# fpga32-serdes-power.net
KiCad netlist of a schematic drawn in Altium Designer
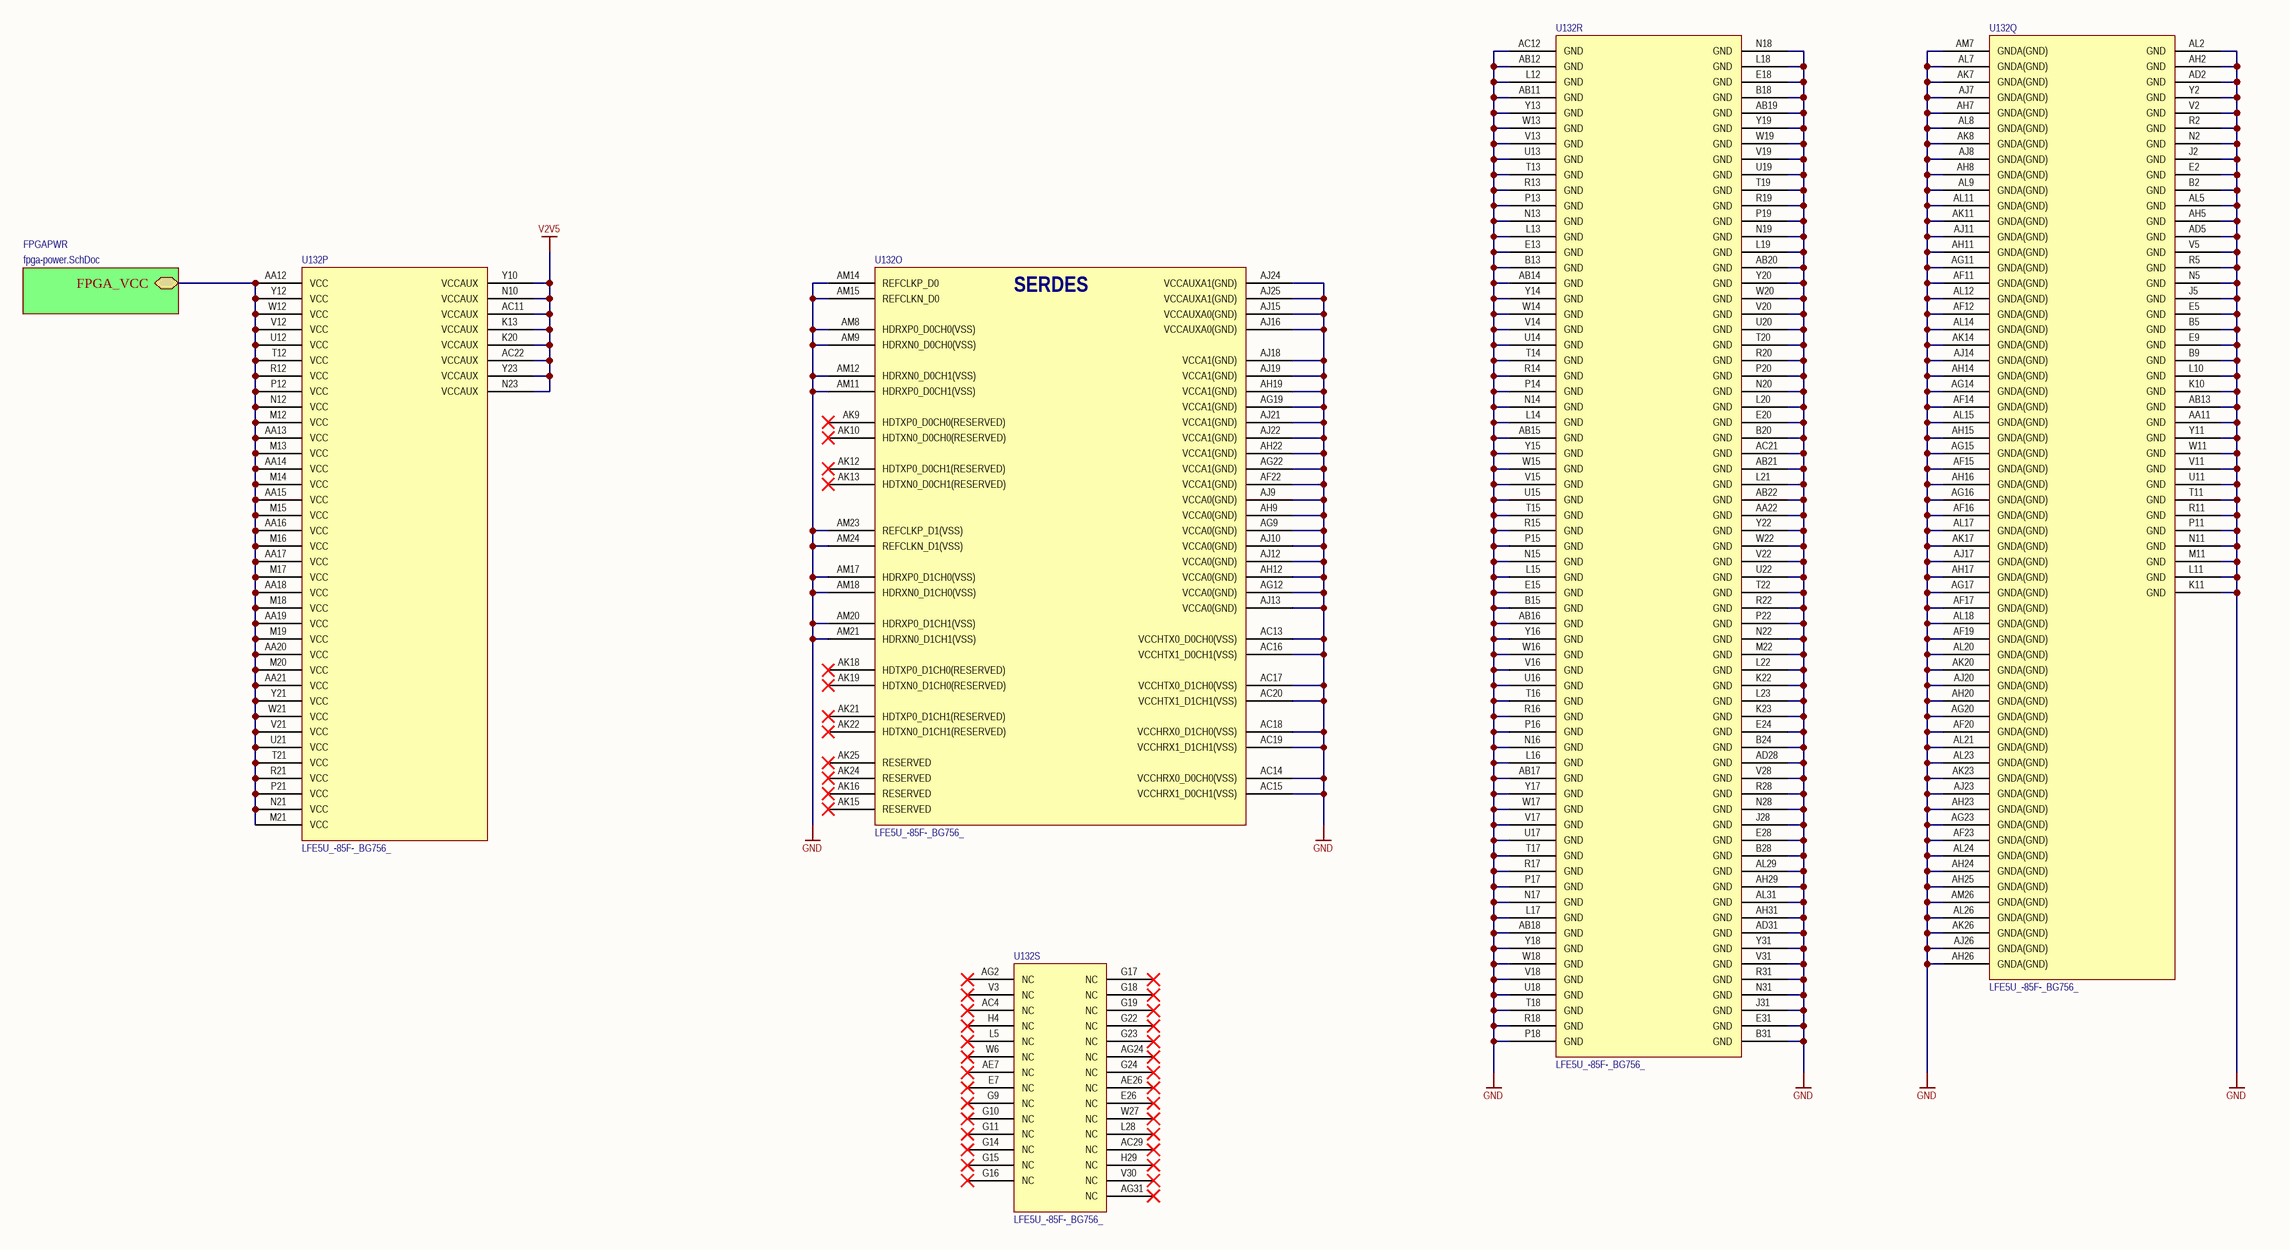
[diagram p0: fpga32-serdes-power.SchDoc]

(export (version "E")
  (design (tool "Eeschema 10.0.6"))
  (components
    (comp (ref "U132")
      (value "LFE5U_-85F-_BG756_")
      (footprint "lattice:caBGA756")
      (description "ECP5 FPGA, 85k LUT, 756-caBGA")
      (fields (field (name "MANUFACTURER") "Lattice Semiconductor"))
      (libsource (lib "lattice") (part "LFE5U_-85F-_BG756_"))
    )
  )
  (nets
    (net (code "1") (name "/FPGA_VCC") (class "Default")
      (node (ref "U132") (pin "AA12") (pinfunction "VCC_AA12") (pintype "power_in"))
      (node (ref "U132") (pin "AA13") (pinfunction "VCC_AA13") (pintype "power_in"))
      (node (ref "U132") (pin "AA14") (pinfunction "VCC_AA14") (pintype "power_in"))
      (node (ref "U132") (pin "AA15") (pinfunction "VCC_AA15") (pintype "power_in"))
      (node (ref "U132") (pin "AA16") (pinfunction "VCC_AA16") (pintype "power_in"))
      (node (ref "U132") (pin "AA17") (pinfunction "VCC_AA17") (pintype "power_in"))
      (node (ref "U132") (pin "AA18") (pinfunction "VCC_AA18") (pintype "power_in"))
      (node (ref "U132") (pin "AA19") (pinfunction "VCC_AA19") (pintype "power_in"))
      (node (ref "U132") (pin "AA20") (pinfunction "VCC_AA20") (pintype "power_in"))
      (node (ref "U132") (pin "AA21") (pinfunction "VCC_AA21") (pintype "power_in"))
      (node (ref "U132") (pin "M12") (pinfunction "VCC_M12") (pintype "power_in"))
      (node (ref "U132") (pin "M13") (pinfunction "VCC_M13") (pintype "power_in"))
      (node (ref "U132") (pin "M14") (pinfunction "VCC_M14") (pintype "power_in"))
      (node (ref "U132") (pin "M15") (pinfunction "VCC_M15") (pintype "power_in"))
      (node (ref "U132") (pin "M16") (pinfunction "VCC_M16") (pintype "power_in"))
      (node (ref "U132") (pin "M17") (pinfunction "VCC_M17") (pintype "power_in"))
      (node (ref "U132") (pin "M18") (pinfunction "VCC_M18") (pintype "power_in"))
      (node (ref "U132") (pin "M19") (pinfunction "VCC_M19") (pintype "power_in"))
      (node (ref "U132") (pin "M20") (pinfunction "VCC_M20") (pintype "power_in"))
      (node (ref "U132") (pin "M21") (pinfunction "VCC_M21") (pintype "power_in"))
      (node (ref "U132") (pin "N12") (pinfunction "VCC_N12") (pintype "power_in"))
      (node (ref "U132") (pin "N21") (pinfunction "VCC_N21") (pintype "power_in"))
      (node (ref "U132") (pin "P12") (pinfunction "VCC_P12") (pintype "power_in"))
      (node (ref "U132") (pin "P21") (pinfunction "VCC_P21") (pintype "power_in"))
      (node (ref "U132") (pin "R12") (pinfunction "VCC_R12") (pintype "power_in"))
      (node (ref "U132") (pin "R21") (pinfunction "VCC_R21") (pintype "power_in"))
      (node (ref "U132") (pin "T12") (pinfunction "VCC_T12") (pintype "power_in"))
      (node (ref "U132") (pin "T21") (pinfunction "VCC_T21") (pintype "power_in"))
      (node (ref "U132") (pin "U12") (pinfunction "VCC_U12") (pintype "power_in"))
      (node (ref "U132") (pin "U21") (pinfunction "VCC_U21") (pintype "power_in"))
      (node (ref "U132") (pin "V12") (pinfunction "VCC_V12") (pintype "power_in"))
      (node (ref "U132") (pin "V21") (pinfunction "VCC_V21") (pintype "power_in"))
      (node (ref "U132") (pin "W12") (pinfunction "VCC_W12") (pintype "power_in"))
      (node (ref "U132") (pin "W21") (pinfunction "VCC_W21") (pintype "power_in"))
      (node (ref "U132") (pin "Y12") (pinfunction "VCC_Y12") (pintype "power_in"))
      (node (ref "U132") (pin "Y21") (pinfunction "VCC_Y21") (pintype "power_in"))
    )
    (net (code "2") (name "GND") (class "Default")
      (node (ref "U132") (pin "AA11") (pinfunction "GND_AA11") (pintype "power_in"))
      (node (ref "U132") (pin "AA22") (pinfunction "GND_AA22") (pintype "power_in"))
      (node (ref "U132") (pin "AB11") (pinfunction "GND_AB11") (pintype "power_in"))
      (node (ref "U132") (pin "AB12") (pinfunction "GND_AB12") (pintype "power_in"))
      (node (ref "U132") (pin "AB13") (pinfunction "GND_AB13") (pintype "power_in"))
      (node (ref "U132") (pin "AB14") (pinfunction "GND_AB14") (pintype "power_in"))
      (node (ref "U132") (pin "AB15") (pinfunction "GND_AB15") (pintype "power_in"))
      (node (ref "U132") (pin "AB16") (pinfunction "GND_AB16") (pintype "power_in"))
      (node (ref "U132") (pin "AB17") (pinfunction "GND_AB17") (pintype "power_in"))
      (node (ref "U132") (pin "AB18") (pinfunction "GND_AB18") (pintype "power_in"))
      (node (ref "U132") (pin "AB19") (pinfunction "GND_AB19") (pintype "power_in"))
      (node (ref "U132") (pin "AB20") (pinfunction "GND_AB20") (pintype "power_in"))
      (node (ref "U132") (pin "AB21") (pinfunction "GND_AB21") (pintype "power_in"))
      (node (ref "U132") (pin "AB22") (pinfunction "GND_AB22") (pintype "power_in"))
      (node (ref "U132") (pin "AC12") (pinfunction "GND_AC12") (pintype "power_in"))
      (node (ref "U132") (pin "AC13") (pinfunction "VCCHTX0_D0CH0(VSS)_AC13") (pintype "power_in"))
      (node (ref "U132") (pin "AC14") (pinfunction "VCCHRX0_D0CH0(VSS)_AC14") (pintype "power_in"))
      (node (ref "U132") (pin "AC15") (pinfunction "VCCHRX1_D0CH1(VSS)_AC15") (pintype "power_in"))
      (node (ref "U132") (pin "AC16") (pinfunction "VCCHTX1_D0CH1(VSS)_AC16") (pintype "power_in"))
      (node (ref "U132") (pin "AC17") (pinfunction "VCCHTX0_D1CH0(VSS)_AC17") (pintype "power_in"))
      (node (ref "U132") (pin "AC18") (pinfunction "VCCHRX0_D1CH0(VSS)_AC18") (pintype "power_in"))
      (node (ref "U132") (pin "AC19") (pinfunction "VCCHRX1_D1CH1(VSS)_AC19") (pintype "power_in"))
      (node (ref "U132") (pin "AC20") (pinfunction "VCCHTX1_D1CH1(VSS)_AC20") (pintype "power_in"))
      (node (ref "U132") (pin "AC21") (pinfunction "GND_AC21") (pintype "power_in"))
      (node (ref "U132") (pin "AD2") (pinfunction "GND_AD2") (pintype "power_in"))
      (node (ref "U132") (pin "AD28") (pinfunction "GND_AD28") (pintype "power_in"))
      (node (ref "U132") (pin "AD31") (pinfunction "GND_AD31") (pintype "power_in"))
      (node (ref "U132") (pin "AD5") (pinfunction "GND_AD5") (pintype "power_in"))
      (node (ref "U132") (pin "AF11") (pinfunction "GNDA(GND)_AF11") (pintype "power_in"))
      (node (ref "U132") (pin "AF12") (pinfunction "GNDA(GND)_AF12") (pintype "power_in"))
      (node (ref "U132") (pin "AF14") (pinfunction "GNDA(GND)_AF14") (pintype "power_in"))
      (node (ref "U132") (pin "AF15") (pinfunction "GNDA(GND)_AF15") (pintype "power_in"))
      (node (ref "U132") (pin "AF16") (pinfunction "GNDA(GND)_AF16") (pintype "power_in"))
      (node (ref "U132") (pin "AF17") (pinfunction "GNDA(GND)_AF17") (pintype "power_in"))
      (node (ref "U132") (pin "AF19") (pinfunction "GNDA(GND)_AF19") (pintype "power_in"))
      (node (ref "U132") (pin "AF20") (pinfunction "GNDA(GND)_AF20") (pintype "power_in"))
      (node (ref "U132") (pin "AF22") (pinfunction "VCCA1(GND)_AF22") (pintype "power_in"))
      (node (ref "U132") (pin "AF23") (pinfunction "GNDA(GND)_AF23") (pintype "power_in"))
      (node (ref "U132") (pin "AG11") (pinfunction "GNDA(GND)_AG11") (pintype "power_in"))
      (node (ref "U132") (pin "AG12") (pinfunction "VCCA0(GND)_AG12") (pintype "power_in"))
      (node (ref "U132") (pin "AG14") (pinfunction "GNDA(GND)_AG14") (pintype "power_in"))
      (node (ref "U132") (pin "AG15") (pinfunction "GNDA(GND)_AG15") (pintype "power_in"))
      (node (ref "U132") (pin "AG16") (pinfunction "GNDA(GND)_AG16") (pintype "power_in"))
      (node (ref "U132") (pin "AG17") (pinfunction "GNDA(GND)_AG17") (pintype "power_in"))
      (node (ref "U132") (pin "AG19") (pinfunction "VCCA1(GND)_AG19") (pintype "power_in"))
      (node (ref "U132") (pin "AG20") (pinfunction "GNDA(GND)_AG20") (pintype "power_in"))
      (node (ref "U132") (pin "AG22") (pinfunction "VCCA1(GND)_AG22") (pintype "power_in"))
      (node (ref "U132") (pin "AG23") (pinfunction "GNDA(GND)_AG23") (pintype "power_in"))
      (node (ref "U132") (pin "AG9") (pinfunction "VCCA0(GND)_AG9") (pintype "power_in"))
      (node (ref "U132") (pin "AH11") (pinfunction "GNDA(GND)_AH11") (pintype "power_in"))
      (node (ref "U132") (pin "AH12") (pinfunction "VCCA0(GND)_AH12") (pintype "power_in"))
      (node (ref "U132") (pin "AH14") (pinfunction "GNDA(GND)_AH14") (pintype "power_in"))
      (node (ref "U132") (pin "AH15") (pinfunction "GNDA(GND)_AH15") (pintype "power_in"))
      (node (ref "U132") (pin "AH16") (pinfunction "GNDA(GND)_AH16") (pintype "power_in"))
      (node (ref "U132") (pin "AH17") (pinfunction "GNDA(GND)_AH17") (pintype "power_in"))
      (node (ref "U132") (pin "AH19") (pinfunction "VCCA1(GND)_AH19") (pintype "power_in"))
      (node (ref "U132") (pin "AH2") (pinfunction "GND_AH2") (pintype "power_in"))
      (node (ref "U132") (pin "AH20") (pinfunction "GNDA(GND)_AH20") (pintype "power_in"))
      (node (ref "U132") (pin "AH22") (pinfunction "VCCA1(GND)_AH22") (pintype "power_in"))
      (node (ref "U132") (pin "AH23") (pinfunction "GNDA(GND)_AH23") (pintype "power_in"))
      (node (ref "U132") (pin "AH24") (pinfunction "GNDA(GND)_AH24") (pintype "power_in"))
      (node (ref "U132") (pin "AH25") (pinfunction "GNDA(GND)_AH25") (pintype "power_in"))
      (node (ref "U132") (pin "AH26") (pinfunction "GNDA(GND)_AH26") (pintype "power_in"))
      (node (ref "U132") (pin "AH29") (pinfunction "GND_AH29") (pintype "power_in"))
      (node (ref "U132") (pin "AH31") (pinfunction "GND_AH31") (pintype "power_in"))
      (node (ref "U132") (pin "AH5") (pinfunction "GND_AH5") (pintype "power_in"))
      (node (ref "U132") (pin "AH7") (pinfunction "GNDA(GND)_AH7") (pintype "power_in"))
      (node (ref "U132") (pin "AH8") (pinfunction "GNDA(GND)_AH8") (pintype "power_in"))
      (node (ref "U132") (pin "AH9") (pinfunction "VCCA0(GND)_AH9") (pintype "power_in"))
      (node (ref "U132") (pin "AJ10") (pinfunction "VCCA0(GND)_AJ10") (pintype "power_in"))
      (node (ref "U132") (pin "AJ11") (pinfunction "GNDA(GND)_AJ11") (pintype "power_in"))
      (node (ref "U132") (pin "AJ12") (pinfunction "VCCA0(GND)_AJ12") (pintype "power_in"))
      (node (ref "U132") (pin "AJ13") (pinfunction "VCCA0(GND)_AJ13") (pintype "power_in"))
      (node (ref "U132") (pin "AJ14") (pinfunction "GNDA(GND)_AJ14") (pintype "power_in"))
      (node (ref "U132") (pin "AJ15") (pinfunction "VCCAUXA0(GND)_AJ15") (pintype "power_in"))
      (node (ref "U132") (pin "AJ16") (pinfunction "VCCAUXA0(GND)_AJ16") (pintype "power_in"))
      (node (ref "U132") (pin "AJ17") (pinfunction "GNDA(GND)_AJ17") (pintype "power_in"))
      (node (ref "U132") (pin "AJ18") (pinfunction "VCCA1(GND)_AJ18") (pintype "power_in"))
      (node (ref "U132") (pin "AJ19") (pinfunction "VCCA1(GND)_AJ19") (pintype "power_in"))
      (node (ref "U132") (pin "AJ20") (pinfunction "GNDA(GND)_AJ20") (pintype "power_in"))
      (node (ref "U132") (pin "AJ21") (pinfunction "VCCA1(GND)_AJ21") (pintype "power_in"))
      (node (ref "U132") (pin "AJ22") (pinfunction "VCCA1(GND)_AJ22") (pintype "power_in"))
      (node (ref "U132") (pin "AJ23") (pinfunction "GNDA(GND)_AJ23") (pintype "power_in"))
      (node (ref "U132") (pin "AJ24") (pinfunction "VCCAUXA1(GND)_AJ24") (pintype "power_in"))
      (node (ref "U132") (pin "AJ25") (pinfunction "VCCAUXA1(GND)_AJ25") (pintype "power_in"))
      (node (ref "U132") (pin "AJ26") (pinfunction "GNDA(GND)_AJ26") (pintype "power_in"))
      (node (ref "U132") (pin "AJ7") (pinfunction "GNDA(GND)_AJ7") (pintype "power_in"))
      (node (ref "U132") (pin "AJ8") (pinfunction "GNDA(GND)_AJ8") (pintype "power_in"))
      (node (ref "U132") (pin "AJ9") (pinfunction "VCCA0(GND)_AJ9") (pintype "power_in"))
      (node (ref "U132") (pin "AK11") (pinfunction "GNDA(GND)_AK11") (pintype "power_in"))
      (node (ref "U132") (pin "AK14") (pinfunction "GNDA(GND)_AK14") (pintype "power_in"))
      (node (ref "U132") (pin "AK17") (pinfunction "GNDA(GND)_AK17") (pintype "power_in"))
      (node (ref "U132") (pin "AK20") (pinfunction "GNDA(GND)_AK20") (pintype "power_in"))
      (node (ref "U132") (pin "AK23") (pinfunction "GNDA(GND)_AK23") (pintype "power_in"))
      (node (ref "U132") (pin "AK26") (pinfunction "GNDA(GND)_AK26") (pintype "power_in"))
      (node (ref "U132") (pin "AK7") (pinfunction "GNDA(GND)_AK7") (pintype "power_in"))
      (node (ref "U132") (pin "AK8") (pinfunction "GNDA(GND)_AK8") (pintype "power_in"))
      (node (ref "U132") (pin "AL11") (pinfunction "GNDA(GND)_AL11") (pintype "power_in"))
      (node (ref "U132") (pin "AL12") (pinfunction "GNDA(GND)_AL12") (pintype "power_in"))
      (node (ref "U132") (pin "AL14") (pinfunction "GNDA(GND)_AL14") (pintype "power_in"))
      (node (ref "U132") (pin "AL15") (pinfunction "GNDA(GND)_AL15") (pintype "power_in"))
      (node (ref "U132") (pin "AL17") (pinfunction "GNDA(GND)_AL17") (pintype "power_in"))
      (node (ref "U132") (pin "AL18") (pinfunction "GNDA(GND)_AL18") (pintype "power_in"))
      (node (ref "U132") (pin "AL2") (pinfunction "GND_AL2") (pintype "power_in"))
      (node (ref "U132") (pin "AL20") (pinfunction "GNDA(GND)_AL20") (pintype "power_in"))
      (node (ref "U132") (pin "AL21") (pinfunction "GNDA(GND)_AL21") (pintype "power_in"))
      (node (ref "U132") (pin "AL23") (pinfunction "GNDA(GND)_AL23") (pintype "power_in"))
      (node (ref "U132") (pin "AL24") (pinfunction "GNDA(GND)_AL24") (pintype "power_in"))
      (node (ref "U132") (pin "AL26") (pinfunction "GNDA(GND)_AL26") (pintype "power_in"))
      (node (ref "U132") (pin "AL29") (pinfunction "GND_AL29") (pintype "power_in"))
      (node (ref "U132") (pin "AL31") (pinfunction "GND_AL31") (pintype "power_in"))
      (node (ref "U132") (pin "AL5") (pinfunction "GND_AL5") (pintype "power_in"))
      (node (ref "U132") (pin "AL7") (pinfunction "GNDA(GND)_AL7") (pintype "power_in"))
      (node (ref "U132") (pin "AL8") (pinfunction "GNDA(GND)_AL8") (pintype "power_in"))
      (node (ref "U132") (pin "AL9") (pinfunction "GNDA(GND)_AL9") (pintype "power_in"))
      (node (ref "U132") (pin "AM11") (pinfunction "HDRXP0_D0CH1(VSS)_AM11") (pintype "passive"))
      (node (ref "U132") (pin "AM12") (pinfunction "HDRXN0_D0CH1(VSS)_AM12") (pintype "passive"))
      (node (ref "U132") (pin "AM14") (pinfunction "REFCLKP_D0_AM14") (pintype "passive"))
      (node (ref "U132") (pin "AM15") (pinfunction "REFCLKN_D0_AM15") (pintype "passive"))
      (node (ref "U132") (pin "AM17") (pinfunction "HDRXP0_D1CH0(VSS)_AM17") (pintype "passive"))
      (node (ref "U132") (pin "AM18") (pinfunction "HDRXN0_D1CH0(VSS)_AM18") (pintype "passive"))
      (node (ref "U132") (pin "AM20") (pinfunction "HDRXP0_D1CH1(VSS)_AM20") (pintype "passive"))
      (node (ref "U132") (pin "AM21") (pinfunction "HDRXN0_D1CH1(VSS)_AM21") (pintype "passive"))
      (node (ref "U132") (pin "AM23") (pinfunction "REFCLKP_D1(VSS)_AM23") (pintype "passive"))
      (node (ref "U132") (pin "AM24") (pinfunction "REFCLKN_D1(VSS)_AM24") (pintype "passive"))
      (node (ref "U132") (pin "AM26") (pinfunction "GNDA(GND)_AM26") (pintype "power_in"))
      (node (ref "U132") (pin "AM7") (pinfunction "GNDA(GND)_AM7") (pintype "power_in"))
      (node (ref "U132") (pin "AM8") (pinfunction "HDRXP0_D0CH0(VSS)_AM8") (pintype "passive"))
      (node (ref "U132") (pin "AM9") (pinfunction "HDRXN0_D0CH0(VSS)_AM9") (pintype "passive"))
      (node (ref "U132") (pin "B13") (pinfunction "GND_B13") (pintype "power_in"))
      (node (ref "U132") (pin "B15") (pinfunction "GND_B15") (pintype "power_in"))
      (node (ref "U132") (pin "B18") (pinfunction "GND_B18") (pintype "power_in"))
      (node (ref "U132") (pin "B2") (pinfunction "GND_B2") (pintype "power_in"))
      (node (ref "U132") (pin "B20") (pinfunction "GND_B20") (pintype "power_in"))
      (node (ref "U132") (pin "B24") (pinfunction "GND_B24") (pintype "power_in"))
      (node (ref "U132") (pin "B28") (pinfunction "GND_B28") (pintype "power_in"))
      (node (ref "U132") (pin "B31") (pinfunction "GND_B31") (pintype "power_in"))
      (node (ref "U132") (pin "B5") (pinfunction "GND_B5") (pintype "power_in"))
      (node (ref "U132") (pin "B9") (pinfunction "GND_B9") (pintype "power_in"))
      (node (ref "U132") (pin "E13") (pinfunction "GND_E13") (pintype "power_in"))
      (node (ref "U132") (pin "E15") (pinfunction "GND_E15") (pintype "power_in"))
      (node (ref "U132") (pin "E18") (pinfunction "GND_E18") (pintype "power_in"))
      (node (ref "U132") (pin "E2") (pinfunction "GND_E2") (pintype "power_in"))
      (node (ref "U132") (pin "E20") (pinfunction "GND_E20") (pintype "power_in"))
      (node (ref "U132") (pin "E24") (pinfunction "GND_E24") (pintype "power_in"))
      (node (ref "U132") (pin "E28") (pinfunction "GND_E28") (pintype "power_in"))
      (node (ref "U132") (pin "E31") (pinfunction "GND_E31") (pintype "power_in"))
      (node (ref "U132") (pin "E5") (pinfunction "GND_E5") (pintype "power_in"))
      (node (ref "U132") (pin "E9") (pinfunction "GND_E9") (pintype "power_in"))
      (node (ref "U132") (pin "J2") (pinfunction "GND_J2") (pintype "power_in"))
      (node (ref "U132") (pin "J28") (pinfunction "GND_J28") (pintype "power_in"))
      (node (ref "U132") (pin "J31") (pinfunction "GND_J31") (pintype "power_in"))
      (node (ref "U132") (pin "J5") (pinfunction "GND_J5") (pintype "power_in"))
      (node (ref "U132") (pin "K10") (pinfunction "GND_K10") (pintype "power_in"))
      (node (ref "U132") (pin "K11") (pinfunction "GND_K11") (pintype "power_in"))
      (node (ref "U132") (pin "K22") (pinfunction "GND_K22") (pintype "power_in"))
      (node (ref "U132") (pin "K23") (pinfunction "GND_K23") (pintype "power_in"))
      (node (ref "U132") (pin "L10") (pinfunction "GND_L10") (pintype "power_in"))
      (node (ref "U132") (pin "L11") (pinfunction "GND_L11") (pintype "power_in"))
      (node (ref "U132") (pin "L12") (pinfunction "GND_L12") (pintype "power_in"))
      (node (ref "U132") (pin "L13") (pinfunction "GND_L13") (pintype "power_in"))
      (node (ref "U132") (pin "L14") (pinfunction "GND_L14") (pintype "power_in"))
      (node (ref "U132") (pin "L15") (pinfunction "GND_L15") (pintype "power_in"))
      (node (ref "U132") (pin "L16") (pinfunction "GND_L16") (pintype "power_in"))
      (node (ref "U132") (pin "L17") (pinfunction "GND_L17") (pintype "power_in"))
      (node (ref "U132") (pin "L18") (pinfunction "GND_L18") (pintype "power_in"))
      (node (ref "U132") (pin "L19") (pinfunction "GND_L19") (pintype "power_in"))
      (node (ref "U132") (pin "L20") (pinfunction "GND_L20") (pintype "power_in"))
      (node (ref "U132") (pin "L21") (pinfunction "GND_L21") (pintype "power_in"))
      (node (ref "U132") (pin "L22") (pinfunction "GND_L22") (pintype "power_in"))
      (node (ref "U132") (pin "L23") (pinfunction "GND_L23") (pintype "power_in"))
      (node (ref "U132") (pin "M11") (pinfunction "GND_M11") (pintype "power_in"))
      (node (ref "U132") (pin "M22") (pinfunction "GND_M22") (pintype "power_in"))
      (node (ref "U132") (pin "N11") (pinfunction "GND_N11") (pintype "power_in"))
      (node (ref "U132") (pin "N13") (pinfunction "GND_N13") (pintype "power_in"))
      (node (ref "U132") (pin "N14") (pinfunction "GND_N14") (pintype "power_in"))
      (node (ref "U132") (pin "N15") (pinfunction "GND_N15") (pintype "power_in"))
      (node (ref "U132") (pin "N16") (pinfunction "GND_N16") (pintype "power_in"))
      (node (ref "U132") (pin "N17") (pinfunction "GND_N17") (pintype "power_in"))
      (node (ref "U132") (pin "N18") (pinfunction "GND_N18") (pintype "power_in"))
      (node (ref "U132") (pin "N19") (pinfunction "GND_N19") (pintype "power_in"))
      (node (ref "U132") (pin "N2") (pinfunction "GND_N2") (pintype "power_in"))
      (node (ref "U132") (pin "N20") (pinfunction "GND_N20") (pintype "power_in"))
      (node (ref "U132") (pin "N22") (pinfunction "GND_N22") (pintype "power_in"))
      (node (ref "U132") (pin "N28") (pinfunction "GND_N28") (pintype "power_in"))
      (node (ref "U132") (pin "N31") (pinfunction "GND_N31") (pintype "power_in"))
      (node (ref "U132") (pin "N5") (pinfunction "GND_N5") (pintype "power_in"))
      (node (ref "U132") (pin "P11") (pinfunction "GND_P11") (pintype "power_in"))
      (node (ref "U132") (pin "P13") (pinfunction "GND_P13") (pintype "power_in"))
      (node (ref "U132") (pin "P14") (pinfunction "GND_P14") (pintype "power_in"))
      (node (ref "U132") (pin "P15") (pinfunction "GND_P15") (pintype "power_in"))
      (node (ref "U132") (pin "P16") (pinfunction "GND_P16") (pintype "power_in"))
      (node (ref "U132") (pin "P17") (pinfunction "GND_P17") (pintype "power_in"))
      (node (ref "U132") (pin "P18") (pinfunction "GND_P18") (pintype "power_in"))
      (node (ref "U132") (pin "P19") (pinfunction "GND_P19") (pintype "power_in"))
      (node (ref "U132") (pin "P20") (pinfunction "GND_P20") (pintype "power_in"))
      (node (ref "U132") (pin "P22") (pinfunction "GND_P22") (pintype "power_in"))
      (node (ref "U132") (pin "R11") (pinfunction "GND_R11") (pintype "power_in"))
      (node (ref "U132") (pin "R13") (pinfunction "GND_R13") (pintype "power_in"))
      (node (ref "U132") (pin "R14") (pinfunction "GND_R14") (pintype "power_in"))
      (node (ref "U132") (pin "R15") (pinfunction "GND_R15") (pintype "power_in"))
      (node (ref "U132") (pin "R16") (pinfunction "GND_R16") (pintype "power_in"))
      (node (ref "U132") (pin "R17") (pinfunction "GND_R17") (pintype "power_in"))
      (node (ref "U132") (pin "R18") (pinfunction "GND_R18") (pintype "power_in"))
      (node (ref "U132") (pin "R19") (pinfunction "GND_R19") (pintype "power_in"))
      (node (ref "U132") (pin "R2") (pinfunction "GND_R2") (pintype "power_in"))
      (node (ref "U132") (pin "R20") (pinfunction "GND_R20") (pintype "power_in"))
      (node (ref "U132") (pin "R22") (pinfunction "GND_R22") (pintype "power_in"))
      (node (ref "U132") (pin "R28") (pinfunction "GND_R28") (pintype "power_in"))
      (node (ref "U132") (pin "R31") (pinfunction "GND_R31") (pintype "power_in"))
      (node (ref "U132") (pin "R5") (pinfunction "GND_R5") (pintype "power_in"))
      (node (ref "U132") (pin "T11") (pinfunction "GND_T11") (pintype "power_in"))
      (node (ref "U132") (pin "T13") (pinfunction "GND_T13") (pintype "power_in"))
      (node (ref "U132") (pin "T14") (pinfunction "GND_T14") (pintype "power_in"))
      (node (ref "U132") (pin "T15") (pinfunction "GND_T15") (pintype "power_in"))
      (node (ref "U132") (pin "T16") (pinfunction "GND_T16") (pintype "power_in"))
      (node (ref "U132") (pin "T17") (pinfunction "GND_T17") (pintype "power_in"))
      (node (ref "U132") (pin "T18") (pinfunction "GND_T18") (pintype "power_in"))
      (node (ref "U132") (pin "T19") (pinfunction "GND_T19") (pintype "power_in"))
      (node (ref "U132") (pin "T20") (pinfunction "GND_T20") (pintype "power_in"))
      (node (ref "U132") (pin "T22") (pinfunction "GND_T22") (pintype "power_in"))
      (node (ref "U132") (pin "U11") (pinfunction "GND_U11") (pintype "power_in"))
      (node (ref "U132") (pin "U13") (pinfunction "GND_U13") (pintype "power_in"))
      (node (ref "U132") (pin "U14") (pinfunction "GND_U14") (pintype "power_in"))
      (node (ref "U132") (pin "U15") (pinfunction "GND_U15") (pintype "power_in"))
      (node (ref "U132") (pin "U16") (pinfunction "GND_U16") (pintype "power_in"))
      (node (ref "U132") (pin "U17") (pinfunction "GND_U17") (pintype "power_in"))
      (node (ref "U132") (pin "U18") (pinfunction "GND_U18") (pintype "power_in"))
      (node (ref "U132") (pin "U19") (pinfunction "GND_U19") (pintype "power_in"))
      (node (ref "U132") (pin "U20") (pinfunction "GND_U20") (pintype "power_in"))
      (node (ref "U132") (pin "U22") (pinfunction "GND_U22") (pintype "power_in"))
      (node (ref "U132") (pin "V11") (pinfunction "GND_V11") (pintype "power_in"))
      (node (ref "U132") (pin "V13") (pinfunction "GND_V13") (pintype "power_in"))
      (node (ref "U132") (pin "V14") (pinfunction "GND_V14") (pintype "power_in"))
      (node (ref "U132") (pin "V15") (pinfunction "GND_V15") (pintype "power_in"))
      (node (ref "U132") (pin "V16") (pinfunction "GND_V16") (pintype "power_in"))
      (node (ref "U132") (pin "V17") (pinfunction "GND_V17") (pintype "power_in"))
      (node (ref "U132") (pin "V18") (pinfunction "GND_V18") (pintype "power_in"))
      (node (ref "U132") (pin "V19") (pinfunction "GND_V19") (pintype "power_in"))
      (node (ref "U132") (pin "V2") (pinfunction "GND_V2") (pintype "power_in"))
      (node (ref "U132") (pin "V20") (pinfunction "GND_V20") (pintype "power_in"))
      (node (ref "U132") (pin "V22") (pinfunction "GND_V22") (pintype "power_in"))
      (node (ref "U132") (pin "V28") (pinfunction "GND_V28") (pintype "power_in"))
      (node (ref "U132") (pin "V31") (pinfunction "GND_V31") (pintype "power_in"))
      (node (ref "U132") (pin "V5") (pinfunction "GND_V5") (pintype "power_in"))
      (node (ref "U132") (pin "W11") (pinfunction "GND_W11") (pintype "power_in"))
      (node (ref "U132") (pin "W13") (pinfunction "GND_W13") (pintype "power_in"))
      (node (ref "U132") (pin "W14") (pinfunction "GND_W14") (pintype "power_in"))
      (node (ref "U132") (pin "W15") (pinfunction "GND_W15") (pintype "power_in"))
      (node (ref "U132") (pin "W16") (pinfunction "GND_W16") (pintype "power_in"))
      (node (ref "U132") (pin "W17") (pinfunction "GND_W17") (pintype "power_in"))
      (node (ref "U132") (pin "W18") (pinfunction "GND_W18") (pintype "power_in"))
      (node (ref "U132") (pin "W19") (pinfunction "GND_W19") (pintype "power_in"))
      (node (ref "U132") (pin "W20") (pinfunction "GND_W20") (pintype "power_in"))
      (node (ref "U132") (pin "W22") (pinfunction "GND_W22") (pintype "power_in"))
      (node (ref "U132") (pin "Y11") (pinfunction "GND_Y11") (pintype "power_in"))
      (node (ref "U132") (pin "Y13") (pinfunction "GND_Y13") (pintype "power_in"))
      (node (ref "U132") (pin "Y14") (pinfunction "GND_Y14") (pintype "power_in"))
      (node (ref "U132") (pin "Y15") (pinfunction "GND_Y15") (pintype "power_in"))
      (node (ref "U132") (pin "Y16") (pinfunction "GND_Y16") (pintype "power_in"))
      (node (ref "U132") (pin "Y17") (pinfunction "GND_Y17") (pintype "power_in"))
      (node (ref "U132") (pin "Y18") (pinfunction "GND_Y18") (pintype "power_in"))
      (node (ref "U132") (pin "Y19") (pinfunction "GND_Y19") (pintype "power_in"))
      (node (ref "U132") (pin "Y2") (pinfunction "GND_Y2") (pintype "power_in"))
      (node (ref "U132") (pin "Y20") (pinfunction "GND_Y20") (pintype "power_in"))
      (node (ref "U132") (pin "Y22") (pinfunction "GND_Y22") (pintype "power_in"))
      (node (ref "U132") (pin "Y31") (pinfunction "GND_Y31") (pintype "power_in"))
    )
    (net (code "3") (name "V2V5") (class "Default")
      (node (ref "U132") (pin "AC11") (pinfunction "VCCAUX_AC11") (pintype "power_in"))
      (node (ref "U132") (pin "AC22") (pinfunction "VCCAUX_AC22") (pintype "power_in"))
      (node (ref "U132") (pin "K13") (pinfunction "VCCAUX_K13") (pintype "power_in"))
      (node (ref "U132") (pin "K20") (pinfunction "VCCAUX_K20") (pintype "power_in"))
      (node (ref "U132") (pin "N10") (pinfunction "VCCAUX_N10") (pintype "power_in"))
      (node (ref "U132") (pin "N23") (pinfunction "VCCAUX_N23") (pintype "power_in"))
      (node (ref "U132") (pin "Y10") (pinfunction "VCCAUX_Y10") (pintype "power_in"))
      (node (ref "U132") (pin "Y23") (pinfunction "VCCAUX_Y23") (pintype "power_in"))
    )
    (net (code "4") (name "unconnected-(U132O-HDTXN0_D0CH0(RESERVED)-PadAK10)") (class "Default")
      (node (ref "U132") (pin "AK10") (pinfunction "HDTXN0_D0CH0(RESERVED)_AK10") (pintype "passive+no_connect"))
    )
    (net (code "5") (name "unconnected-(U132O-HDTXN0_D0CH1(RESERVED)-PadAK13)") (class "Default")
      (node (ref "U132") (pin "AK13") (pinfunction "HDTXN0_D0CH1(RESERVED)_AK13") (pintype "passive+no_connect"))
    )
    (net (code "6") (name "unconnected-(U132O-HDTXN0_D1CH0(RESERVED)-PadAK19)") (class "Default")
      (node (ref "U132") (pin "AK19") (pinfunction "HDTXN0_D1CH0(RESERVED)_AK19") (pintype "passive+no_connect"))
    )
    (net (code "7") (name "unconnected-(U132O-HDTXN0_D1CH1(RESERVED)-PadAK22)") (class "Default")
      (node (ref "U132") (pin "AK22") (pinfunction "HDTXN0_D1CH1(RESERVED)_AK22") (pintype "passive+no_connect"))
    )
    (net (code "8") (name "unconnected-(U132O-HDTXP0_D0CH0(RESERVED)-PadAK9)") (class "Default")
      (node (ref "U132") (pin "AK9") (pinfunction "HDTXP0_D0CH0(RESERVED)_AK9") (pintype "passive+no_connect"))
    )
    (net (code "9") (name "unconnected-(U132O-HDTXP0_D0CH1(RESERVED)-PadAK12)") (class "Default")
      (node (ref "U132") (pin "AK12") (pinfunction "HDTXP0_D0CH1(RESERVED)_AK12") (pintype "passive+no_connect"))
    )
    (net (code "10") (name "unconnected-(U132O-HDTXP0_D1CH0(RESERVED)-PadAK18)") (class "Default")
      (node (ref "U132") (pin "AK18") (pinfunction "HDTXP0_D1CH0(RESERVED)_AK18") (pintype "passive+no_connect"))
    )
    (net (code "11") (name "unconnected-(U132O-HDTXP0_D1CH1(RESERVED)-PadAK21)") (class "Default")
      (node (ref "U132") (pin "AK21") (pinfunction "HDTXP0_D1CH1(RESERVED)_AK21") (pintype "passive+no_connect"))
    )
    (net (code "12") (name "unconnected-(U132O-RESERVED-PadAK15)") (class "Default")
      (node (ref "U132") (pin "AK15") (pinfunction "RESERVED_AK15") (pintype "passive+no_connect"))
    )
    (net (code "13") (name "unconnected-(U132O-RESERVED-PadAK16)") (class "Default")
      (node (ref "U132") (pin "AK16") (pinfunction "RESERVED_AK16") (pintype "passive+no_connect"))
    )
    (net (code "14") (name "unconnected-(U132O-RESERVED-PadAK24)") (class "Default")
      (node (ref "U132") (pin "AK24") (pinfunction "RESERVED_AK24") (pintype "passive+no_connect"))
    )
    (net (code "15") (name "unconnected-(U132O-RESERVED-PadAK25)") (class "Default")
      (node (ref "U132") (pin "AK25") (pinfunction "RESERVED_AK25") (pintype "passive+no_connect"))
    )
    (net (code "16") (name "unconnected-(U132S-NC-PadAC4)") (class "Default")
      (node (ref "U132") (pin "AC4") (pinfunction "NC_AC4") (pintype "passive+no_connect"))
    )
    (net (code "17") (name "unconnected-(U132S-NC-PadAC29)") (class "Default")
      (node (ref "U132") (pin "AC29") (pinfunction "NC_AC29") (pintype "passive+no_connect"))
    )
    (net (code "18") (name "unconnected-(U132S-NC-PadAE7)") (class "Default")
      (node (ref "U132") (pin "AE7") (pinfunction "NC_AE7") (pintype "passive+no_connect"))
    )
    (net (code "19") (name "unconnected-(U132S-NC-PadAE26)") (class "Default")
      (node (ref "U132") (pin "AE26") (pinfunction "NC_AE26") (pintype "passive+no_connect"))
    )
    (net (code "20") (name "unconnected-(U132S-NC-PadAG2)") (class "Default")
      (node (ref "U132") (pin "AG2") (pinfunction "NC_AG2") (pintype "passive+no_connect"))
    )
    (net (code "21") (name "unconnected-(U132S-NC-PadAG24)") (class "Default")
      (node (ref "U132") (pin "AG24") (pinfunction "NC_AG24") (pintype "passive+no_connect"))
    )
    (net (code "22") (name "unconnected-(U132S-NC-PadAG31)") (class "Default")
      (node (ref "U132") (pin "AG31") (pinfunction "NC_AG31") (pintype "passive+no_connect"))
    )
    (net (code "23") (name "unconnected-(U132S-NC-PadE7)") (class "Default")
      (node (ref "U132") (pin "E7") (pinfunction "NC_E7") (pintype "passive+no_connect"))
    )
    (net (code "24") (name "unconnected-(U132S-NC-PadE26)") (class "Default")
      (node (ref "U132") (pin "E26") (pinfunction "NC_E26") (pintype "passive+no_connect"))
    )
    (net (code "25") (name "unconnected-(U132S-NC-PadG9)") (class "Default")
      (node (ref "U132") (pin "G9") (pinfunction "NC_G9") (pintype "passive+no_connect"))
    )
    (net (code "26") (name "unconnected-(U132S-NC-PadG10)") (class "Default")
      (node (ref "U132") (pin "G10") (pinfunction "NC_G10") (pintype "passive+no_connect"))
    )
    (net (code "27") (name "unconnected-(U132S-NC-PadG11)") (class "Default")
      (node (ref "U132") (pin "G11") (pinfunction "NC_G11") (pintype "passive+no_connect"))
    )
    (net (code "28") (name "unconnected-(U132S-NC-PadG14)") (class "Default")
      (node (ref "U132") (pin "G14") (pinfunction "NC_G14") (pintype "passive+no_connect"))
    )
    (net (code "29") (name "unconnected-(U132S-NC-PadG15)") (class "Default")
      (node (ref "U132") (pin "G15") (pinfunction "NC_G15") (pintype "passive+no_connect"))
    )
    (net (code "30") (name "unconnected-(U132S-NC-PadG16)") (class "Default")
      (node (ref "U132") (pin "G16") (pinfunction "NC_G16") (pintype "passive+no_connect"))
    )
    (net (code "31") (name "unconnected-(U132S-NC-PadG17)") (class "Default")
      (node (ref "U132") (pin "G17") (pinfunction "NC_G17") (pintype "passive+no_connect"))
    )
    (net (code "32") (name "unconnected-(U132S-NC-PadG18)") (class "Default")
      (node (ref "U132") (pin "G18") (pinfunction "NC_G18") (pintype "passive+no_connect"))
    )
    (net (code "33") (name "unconnected-(U132S-NC-PadG19)") (class "Default")
      (node (ref "U132") (pin "G19") (pinfunction "NC_G19") (pintype "passive+no_connect"))
    )
    (net (code "34") (name "unconnected-(U132S-NC-PadG22)") (class "Default")
      (node (ref "U132") (pin "G22") (pinfunction "NC_G22") (pintype "passive+no_connect"))
    )
    (net (code "35") (name "unconnected-(U132S-NC-PadG23)") (class "Default")
      (node (ref "U132") (pin "G23") (pinfunction "NC_G23") (pintype "passive+no_connect"))
    )
    (net (code "36") (name "unconnected-(U132S-NC-PadG24)") (class "Default")
      (node (ref "U132") (pin "G24") (pinfunction "NC_G24") (pintype "passive+no_connect"))
    )
    (net (code "37") (name "unconnected-(U132S-NC-PadH4)") (class "Default")
      (node (ref "U132") (pin "H4") (pinfunction "NC_H4") (pintype "passive+no_connect"))
    )
    (net (code "38") (name "unconnected-(U132S-NC-PadH29)") (class "Default")
      (node (ref "U132") (pin "H29") (pinfunction "NC_H29") (pintype "passive+no_connect"))
    )
    (net (code "39") (name "unconnected-(U132S-NC-PadL5)") (class "Default")
      (node (ref "U132") (pin "L5") (pinfunction "NC_L5") (pintype "passive+no_connect"))
    )
    (net (code "40") (name "unconnected-(U132S-NC-PadL28)") (class "Default")
      (node (ref "U132") (pin "L28") (pinfunction "NC_L28") (pintype "passive+no_connect"))
    )
    (net (code "41") (name "unconnected-(U132S-NC-PadV3)") (class "Default")
      (node (ref "U132") (pin "V3") (pinfunction "NC_V3") (pintype "passive+no_connect"))
    )
    (net (code "42") (name "unconnected-(U132S-NC-PadV30)") (class "Default")
      (node (ref "U132") (pin "V30") (pinfunction "NC_V30") (pintype "passive+no_connect"))
    )
    (net (code "43") (name "unconnected-(U132S-NC-PadW6)") (class "Default")
      (node (ref "U132") (pin "W6") (pinfunction "NC_W6") (pintype "passive+no_connect"))
    )
    (net (code "44") (name "unconnected-(U132S-NC-PadW27)") (class "Default")
      (node (ref "U132") (pin "W27") (pinfunction "NC_W27") (pintype "passive+no_connect"))
    )
  )
)
